# ST_LINK_V2-1.net
KiCad netlist of a schematic drawn in Altium Designer
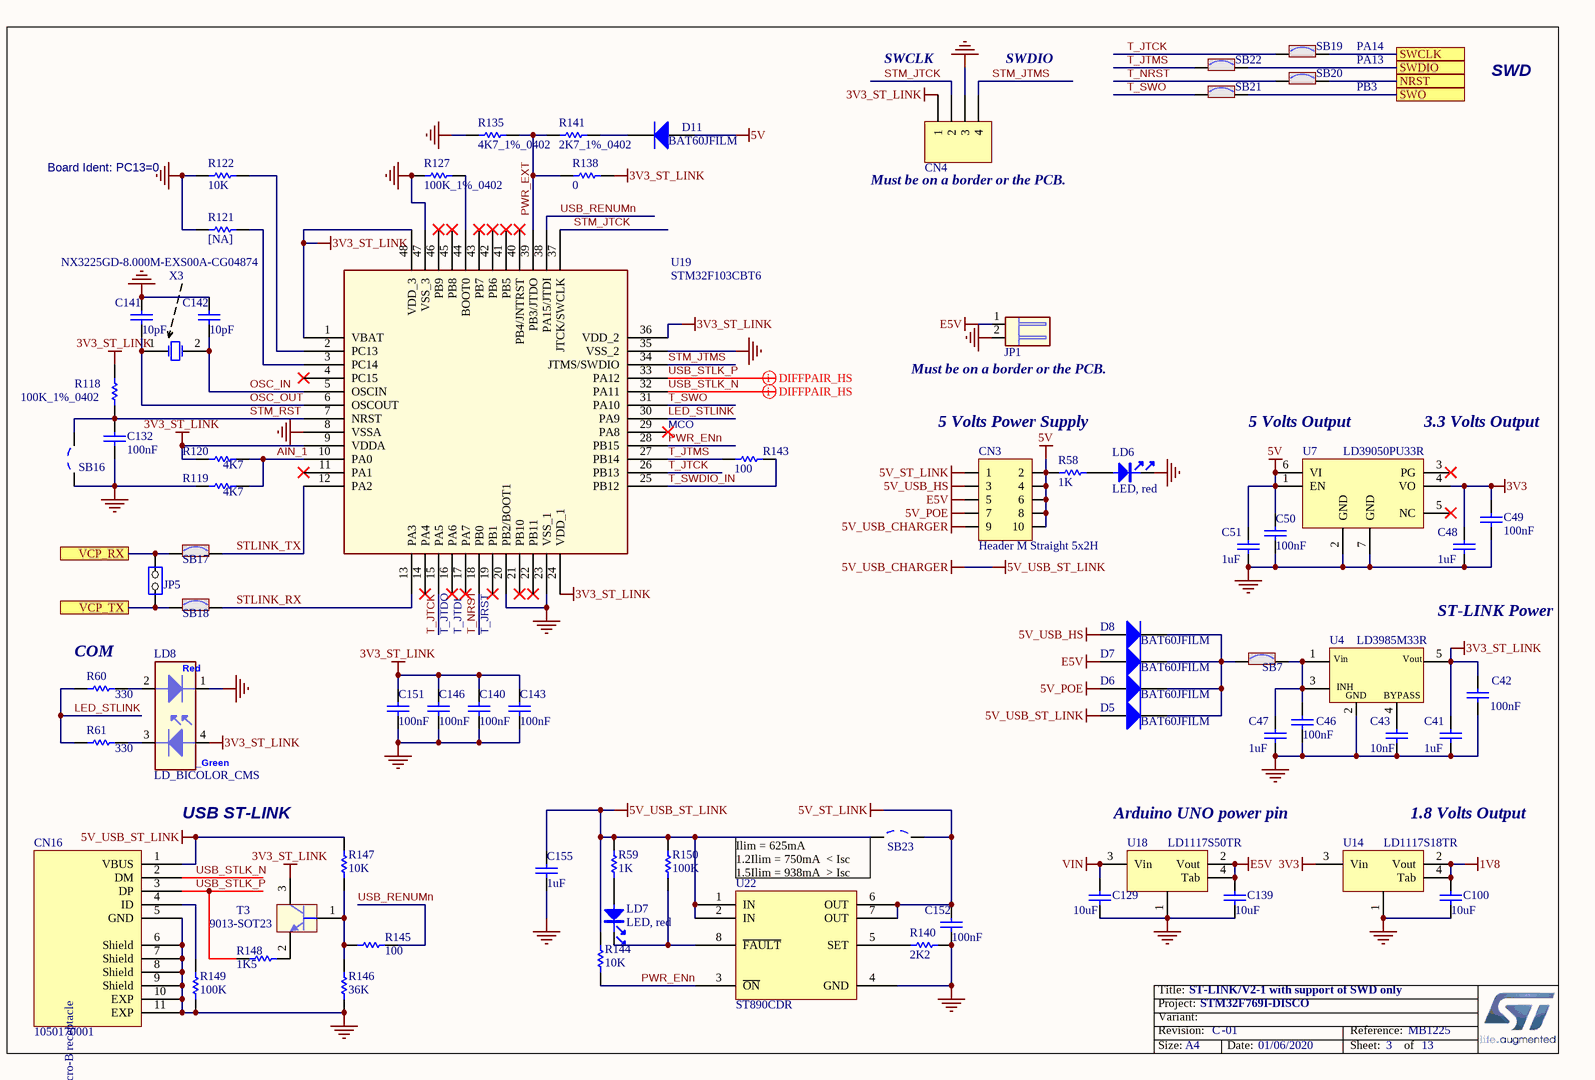
[diagram p0: ST_LINK_V2-1.SCHDOC]

(export (version "E")
  (design (tool "Eeschema 10.0.6"))
  (components
    (comp (ref "C41")
      (value "1uF")
      (footprint "0603C")
      (description "Capacitor,1uF,16V,X5R,10%,0603,YAGEO")
      (libsource (lib "MCD_TOOLS") (part "Cap_1uF_X5R_10%_0603"))
    )
    (comp (ref "C42")
      (value "100nF")
      (footprint "0402C")
      (description "Capacitor,100nF,16V,X7R,10%,0402,YAGEO")
      (libsource (lib "MCD_TOOLS") (part "Cap_100nF_X7R_10%_0402"))
    )
    (comp (ref "C43")
      (value "10nF")
      (footprint "0603C")
      (description "Capacitor,10nF,50V,X7R,10%,0603,YAGEO")
      (libsource (lib "MCD_TOOLS") (part "Cap_10nF_X7R_10%_0603"))
    )
    (comp (ref "C46")
      (value "100nF")
      (footprint "0402C")
      (description "Capacitor,100nF,16V,X7R,10%,0402,YAGEO")
      (libsource (lib "MCD_TOOLS") (part "Cap_100nF_X7R_10%_0402"))
    )
    (comp (ref "C47")
      (value "1uF")
      (footprint "0603C")
      (description "Capacitor,1uF,16V,X5R,10%,0603,YAGEO")
      (libsource (lib "MCD_TOOLS") (part "Cap_1uF_X5R_10%_0603"))
    )
    (comp (ref "C48")
      (value "1uF")
      (footprint "0603C")
      (description "Capacitor,1uF,16V,X5R,10%,0603,YAGEO")
      (libsource (lib "MCD_TOOLS") (part "Cap_1uF_X5R_10%_0603"))
    )
    (comp (ref "C49")
      (value "100nF")
      (footprint "0402C")
      (description "Capacitor,100nF,16V,X7R,10%,0402,YAGEO")
      (libsource (lib "MCD_TOOLS") (part "Cap_100nF_X7R_10%_0402"))
    )
    (comp (ref "C50")
      (value "100nF")
      (footprint "0402C")
      (description "Capacitor,100nF,16V,X7R,10%,0402,YAGEO")
      (libsource (lib "MCD_TOOLS") (part "Cap_100nF_X7R_10%_0402"))
    )
    (comp (ref "C51")
      (value "1uF")
      (footprint "0603C")
      (description "Capacitor,1uF,16V,X5R,10%,0603,YAGEO")
      (libsource (lib "MCD_TOOLS") (part "Cap_1uF_X5R_10%_0603"))
    )
    (comp (ref "C100")
      (value "10uF")
      (footprint "0603C")
      (description "Capacitor,10uF,6.3V,X5R,10%,0603,YAGEO")
      (libsource (lib "MCD_TOOLS") (part "Cap_10uF_X5R_10%_0603"))
    )
    (comp (ref "C129")
      (value "10uF")
      (footprint "0805C")
      (description "Capacitor,10uF,25V,X5R,10%,0805,YAGEO")
      (libsource (lib "MCD_TOOLS") (part "Cap_10uF_X5R_10%_0805"))
    )
    (comp (ref "C132")
      (value "100nF")
      (footprint "0402C")
      (description "Capacitor,100nF,16V,X7R,10%,0402,YAGEO")
      (libsource (lib "MCD_TOOLS") (part "Cap_100nF_X7R_10%_0402"))
    )
    (comp (ref "C139")
      (value "10uF")
      (footprint "0805C")
      (description "Capacitor,10uF,25V,X5R,10%,0805,YAGEO")
      (libsource (lib "MCD_TOOLS") (part "Cap_10uF_X5R_10%_0805"))
    )
    (comp (ref "C140")
      (value "100nF")
      (footprint "0402C")
      (description "Capacitor,100nF,16V,X7R,10%,0402,YAGEO")
      (libsource (lib "MCD_TOOLS") (part "Cap_100nF_X7R_10%_0402"))
    )
    (comp (ref "C141")
      (value "10pF")
      (footprint "0402C")
      (description "Capacitor,10pF,50V,NPO,5%,0402,YAGEO")
      (libsource (lib "MCD_TOOLS") (part "Cap_10pF_NPO_5%_0402"))
    )
    (comp (ref "C142")
      (value "10pF")
      (footprint "0402C")
      (description "Capacitor,10pF,50V,NPO,5%,0402,YAGEO")
      (libsource (lib "MCD_TOOLS") (part "Cap_10pF_NPO_5%_0402"))
    )
    (comp (ref "C143")
      (value "100nF")
      (footprint "0402C")
      (description "Capacitor,100nF,16V,X7R,10%,0402,YAGEO")
      (libsource (lib "MCD_TOOLS") (part "Cap_100nF_X7R_10%_0402"))
    )
    (comp (ref "C146")
      (value "100nF")
      (footprint "0402C")
      (description "Capacitor,100nF,16V,X7R,10%,0402,YAGEO")
      (libsource (lib "MCD_TOOLS") (part "Cap_100nF_X7R_10%_0402"))
    )
    (comp (ref "C151")
      (value "100nF")
      (footprint "0402C")
      (description "Capacitor,100nF,16V,X7R,10%,0402,YAGEO")
      (libsource (lib "MCD_TOOLS") (part "Cap_100nF_X7R_10%_0402"))
    )
    (comp (ref "C152")
      (value "100nF")
      (footprint "0402C")
      (description "Capacitor,100nF,16V,X7R,10%,0402,YAGEO")
      (libsource (lib "MCD_TOOLS") (part "Cap_100nF_X7R_10%_0402"))
    )
    (comp (ref "C155")
      (value "1uF")
      (footprint "0603C")
      (description "Capacitor,1uF,16V,X5R,10%,0603,YAGEO")
      (libsource (lib "MCD_TOOLS_CAPACITOR") (part "Cap_1uF_X5R_10%_0603"))
    )
    (comp (ref "CN3")
      (value "Header M Straight 5x2H")
      (footprint "HDR_2X5_2R54")
      (description "Header Male, 5-Pin, Dual row, Straight, AMD")
      (libsource (lib "MCD_TOOLS_CONNECTOR") (part "Header 5X2M"))
    )
    (comp (ref "CN4")
      (value "Header 4")
      (footprint "HDR_1X4_2R54")
      (description "Header, 4-Pin")
      (fields (field (name "PUBLISHER") "Altium Limited"))
      (libsource (lib "MCD_TOOLS_CONNECTOR") (part "Header 4"))
    )
    (comp (ref "CN16")
      (value "1050170001")
      (footprint "MICRO_USB_B_105017")
      (description "USB-MICRO-B, 1050170001, SMT, MOLEX")
      (libsource (lib "MCD_TOOLS_CONNECTOR") (part "1050170001"))
    )
    (comp (ref "D5")
      (value "BAT60JFILM")
      (footprint "SOD-323")
      (libsource (lib "MCD_TOOLS_MISCELLANEOUS") (part "BAT60JFILM"))
    )
    (comp (ref "D6")
      (value "BAT60JFILM")
      (footprint "SOD-323")
      (libsource (lib "MCD_TOOLS_MISCELLANEOUS") (part "BAT60JFILM"))
    )
    (comp (ref "D7")
      (value "BAT60JFILM")
      (footprint "SOD-323")
      (libsource (lib "MCD_TOOLS_MISCELLANEOUS") (part "BAT60JFILM"))
    )
    (comp (ref "D8")
      (value "BAT60JFILM")
      (footprint "SOD-323")
      (libsource (lib "MCD_TOOLS_MISCELLANEOUS") (part "BAT60JFILM"))
    )
    (comp (ref "D11")
      (value "BAT60JFILM")
      (footprint "SOD-323")
      (libsource (lib "MCD_TOOLS_MISCELLANEOUS") (part "BAT60JFILM"))
    )
    (comp (ref "JP1")
      (value "WF25402-06421")
      (footprint "HDR_1X2_2R54_RA_11R35")
      (description "Header, 2-Pins, Single row, Right Angle, 2.54 mm pitch, DIP")
      (libsource (lib "MCD_TOOLS_CONNECTOR") (part "JP2_RA"))
    )
    (comp (ref "JP5") (value "JP2") (footprint "SIP2") (libsource (lib "MCD_TOOLS_CONNECTOR") (part "JP2")))
    (comp (ref "LD6")
      (value "LED, red")
      (footprint "0603D")
      (description "LED, red, 0603")
      (libsource (lib "MCD_TOOLS") (part "LED_red"))
    )
    (comp (ref "LD7")
      (value "LED, red")
      (footprint "0603D")
      (description "LED, red, 0603")
      (libsource (lib "MCD_TOOLS") (part "LED_red"))
    )
    (comp (ref "LD8")
      (value "LD_BICOLOR_CMS")
      (footprint "LED2_3528")
      (description "Bicolor Led")
      (libsource (lib "MCD_TOOLS_MISCELLANEOUS") (part "LD_BICOLOR_CMS"))
    )
    (comp (ref "R58")
      (value "1K")
      (footprint "0402R")
      (description "Resistor,1K,0402,1%,YAGEO")
      (libsource (lib "MCD_TOOLS") (part "Res_1K_1%_0402"))
    )
    (comp (ref "R59")
      (value "1K")
      (footprint "0402R")
      (description "Resistor,1K,0402,1%,YAGEO")
      (libsource (lib "MCD_TOOLS") (part "Res_1K_1%_0402"))
    )
    (comp (ref "R60")
      (value "330")
      (footprint "0402R")
      (description "Resistor,330,0402,1%,YAGEO")
      (libsource (lib "MCD_TOOLS") (part "Res_330_1%_0402"))
    )
    (comp (ref "R61")
      (value "330")
      (footprint "0402R")
      (description "Resistor,330,0402,1%,YAGEO")
      (libsource (lib "MCD_TOOLS") (part "Res_330_1%_0402"))
    )
    (comp (ref "R118")
      (value "100K_1%_0402")
      (footprint "0402R")
      (description "Resistor,100K,0402,1%,YAGEO")
      (libsource (lib "MCD_TOOLS_RESISTOR") (part "Res_100K_1%_0402"))
    )
    (comp (ref "R119")
      (value "4K7")
      (footprint "0402R")
      (description "Resistor,4K7,0402,1%,YAGEO")
      (libsource (lib "MCD_TOOLS_RESISTOR") (part "Res_4K7_1%_0402"))
    )
    (comp (ref "R120")
      (value "4K7")
      (footprint "0402R")
      (description "Resistor,4K7,0402,1%,YAGEO")
      (libsource (lib "MCD_TOOLS_RESISTOR") (part "Res_4K7_1%_0402"))
    )
    (comp (ref "R121")
      (value "[NA]")
      (footprint "0402R")
      (description "Resistor,[NA],0402")
      (libsource (lib "MCD_TOOLS") (part "Res_NA_0402"))
    )
    (comp (ref "R122")
      (value "10K")
      (footprint "0402R")
      (description "Resistor,10K,0402,1%,YAGEO")
      (libsource (lib "MCD_TOOLS") (part "Res_10K_1%_0402"))
    )
    (comp (ref "R127")
      (value "100K_1%_0402")
      (footprint "0402R")
      (description "Resistor,100K,0402,1%,YAGEO")
      (libsource (lib "MCD_TOOLS_RESISTOR") (part "Res_100K_1%_0402"))
    )
    (comp (ref "R135")
      (value "4K7_1%_0402")
      (footprint "0402R")
      (description "Resistor,4K7,0402,1%,YAGEO")
      (libsource (lib "MCD_TOOLS_RESISTOR") (part "Res_4K7_1%_0402"))
    )
    (comp (ref "R138")
      (value "0")
      (footprint "0402R")
      (description "Resistor,0,0402,5%,YAGEO")
      (libsource (lib "MCD_TOOLS") (part "Res_0_5%_0402"))
    )
    (comp (ref "R140")
      (value "2K2")
      (footprint "0402R")
      (description "Resistor,2K2,0402,1%,YAGEO")
      (libsource (lib "MCD_TOOLS_RESISTOR") (part "Res_2K2_1%_0402"))
    )
    (comp (ref "R141")
      (value "2K7_1%_0402")
      (footprint "0402R")
      (description "Resistor,2K7,0402,1%,YAGEO")
      (libsource (lib "MCD_TOOLS_RESISTOR") (part "Res_2K7_1%_0402"))
    )
    (comp (ref "R143")
      (value "100")
      (footprint "0402R")
      (description "Resistor,100,0402,1%,YAGEO")
      (libsource (lib "MCD_TOOLS") (part "Res_100_1%_0402"))
    )
    (comp (ref "R144")
      (value "10K")
      (footprint "0402R")
      (description "Resistor,10K,0402,1%,YAGEO")
      (libsource (lib "MCD_TOOLS") (part "Res_10K_1%_0402"))
    )
    (comp (ref "R145")
      (value "100")
      (footprint "0402R")
      (description "Resistor,100,0402,1%,YAGEO")
      (libsource (lib "MCD_TOOLS") (part "Res_100_1%_0402"))
    )
    (comp (ref "R146")
      (value "36K")
      (footprint "0402R")
      (description "Resistor,36K,0402,1%,YAGEO")
      (libsource (lib "MCD_TOOLS") (part "Res_36K_1%_0402"))
    )
    (comp (ref "R147")
      (value "10K")
      (footprint "0402R")
      (description "Resistor,10K,0402,1%,YAGEO")
      (libsource (lib "MCD_TOOLS") (part "Res_10K_1%_0402"))
    )
    (comp (ref "R148")
      (value "1K5")
      (footprint "0402R")
      (description "Resistor,1K5,0402,1%,YAGEO")
      (libsource (lib "MCD_TOOLS") (part "Res_1K5_1%_0402"))
    )
    (comp (ref "R149")
      (value "100K")
      (footprint "0402R")
      (description "Resistor,100K,0402,1%,YAGEO")
      (libsource (lib "MCD_TOOLS_RESISTOR") (part "Res_100K_1%_0402"))
    )
    (comp (ref "R150")
      (value "100K")
      (footprint "0402R")
      (description "Resistor,100K,0402,1%,YAGEO")
      (libsource (lib "MCD_TOOLS_RESISTOR") (part "Res_100K_1%_0402"))
    )
    (comp (ref "SB7")
      (value "Solder Bridge ON")
      (footprint "JP2_SMD")
      (libsource (lib "MCD_TOOLS") (part "SB_ON"))
    )
    (comp (ref "SB16")
      (value "Solder Bridge OFF")
      (footprint "JP2_SMD")
      (libsource (lib "MCD_TOOLS") (part "SB_OFF"))
    )
    (comp (ref "SB17")
      (value "Solder Bridge ON")
      (footprint "JP2_SMD")
      (libsource (lib "MCD_TOOLS") (part "SB_ON"))
    )
    (comp (ref "SB18")
      (value "Solder Bridge ON")
      (footprint "JP2_SMD")
      (libsource (lib "MCD_TOOLS") (part "SB_ON"))
    )
    (comp (ref "SB19")
      (value "Solder Bridge ON")
      (footprint "JP2_SMD")
      (libsource (lib "MCD_TOOLS") (part "SB_ON"))
    )
    (comp (ref "SB20")
      (value "Solder Bridge ON")
      (footprint "JP2_SMD")
      (libsource (lib "MCD_TOOLS") (part "SB_ON"))
    )
    (comp (ref "SB21")
      (value "Solder Bridge ON")
      (footprint "JP2_SMD")
      (libsource (lib "MCD_TOOLS") (part "SB_ON"))
    )
    (comp (ref "SB22")
      (value "Solder Bridge ON")
      (footprint "JP2_SMD")
      (libsource (lib "MCD_TOOLS") (part "SB_ON"))
    )
    (comp (ref "SB23")
      (value "Solder Bridge OFF")
      (footprint "JP2_SMD")
      (libsource (lib "MCD_TOOLS") (part "SB_OFF"))
    )
    (comp (ref "T3")
      (value "9013-SOT23")
      (footprint "SOT-23")
      (description "NPN Bipolar Transistor")
      (libsource (lib "MCD_TOOLS_MISCELLANEOUS") (part "9013-SOT23"))
    )
    (comp (ref "U4")
      (value "LD3985M33R")
      (footprint "SOT-23-5L")
      (description "Ultra low drop-low noise BiCMOS voltage, regulators low ESR capacitors compatible")
      (libsource (lib "MCD_TOOLS_MISCELLANEOUS") (part "LD3985M33R"))
    )
    (comp (ref "U7")
      (value "LD39050PU33R")
      (footprint "DFN6_0R95_3X3")
      (description "Ultra low drop-low , 500 mA low quiescent current")
      (libsource (lib "mb1225") (part "LD39050P"))
    )
    (comp (ref "U14")
      (value "LD1117S18TR")
      (footprint "SOT-223")
      (description "LOW DROP FIXED AND ADJUSTABLE POSITIVE VOLTAGE REGULATORS (1.8 Volts)")
      (libsource (lib "mb1225") (part "LD1117S18TR"))
    )
    (comp (ref "U18")
      (value "LD1117S50TR")
      (footprint "SOT-223")
      (description "IC REG LDO 5V 0.8A SOT223")
      (libsource (lib "mb1225") (part "LD1117S50TR"))
    )
    (comp (ref "U19")
      (value "STM32F103CBT6")
      (footprint "LQFP48_0R5_9X9")
      (description "Medium-density performance line ARM-based 32-bit MCU with 128KB Flash")
      (libsource (lib "MCD_TOOLS_MCU") (part "STM32F103CBT6"))
    )
    (comp (ref "U22")
      (value "ST890CDR")
      (footprint "SOIC8_1R27_4R9X6")
      (description "1.2 A current limited high-side power switch with thermal shutdown")
      (libsource (lib "mb1225") (part "ST890CDR"))
    )
    (comp (ref "X3")
      (value "NX3225GD-8.000M-EXS00A-CG04874")
      (footprint "XTAL_2SM_3R2X2R5_H1")
      (description "Crystal 8Mhz, 8pF, -+50PPM, SMD")
      (libsource (lib "MCD_TOOLS_MISCELLANEOUS") (part "XTAL_8M_NX3225GD"))
    )
  )
  (nets
    (net (code "1") (name "/AIN_1") (class "Default")
      (node (ref "R119") (pin "2") (pinfunction "2_2") (pintype "passive"))
      (node (ref "R120") (pin "2") (pinfunction "2_2") (pintype "passive"))
      (node (ref "U19") (pin "10") (pinfunction "PA0_10") (pintype "passive"))
    )
    (net (code "2") (name "/LED_STLINK") (class "Default")
      (node (ref "R60") (pin "1") (pinfunction "1_1") (pintype "passive"))
      (node (ref "R61") (pin "1") (pinfunction "1_1") (pintype "passive"))
      (node (ref "U19") (pin "30") (pinfunction "PA9_30") (pintype "passive"))
    )
    (net (code "3") (name "/NRST") (class "Default")
      (node (ref "SB20") (pin "2") (pinfunction "2_2") (pintype "passive"))
    )
    (net (code "4") (name "/OSC_IN") (class "Default")
      (node (ref "C142") (pin "2") (pinfunction "2_2") (pintype "passive"))
      (node (ref "U19") (pin "5") (pinfunction "OSCIN_5") (pintype "passive"))
      (node (ref "X3") (pin "2") (pinfunction "OSC2_2") (pintype "passive"))
    )
    (net (code "5") (name "/OSC_OUT") (class "Default")
      (node (ref "C141") (pin "2") (pinfunction "2_2") (pintype "passive"))
      (node (ref "U19") (pin "6") (pinfunction "OSCOUT_6") (pintype "passive"))
      (node (ref "X3") (pin "1") (pinfunction "OSC1_1") (pintype "passive"))
    )
    (net (code "6") (name "/PWR_ENn") (class "Default")
      (node (ref "R144") (pin "1") (pinfunction "1_1") (pintype "passive"))
      (node (ref "U19") (pin "28") (pinfunction "PB15_28") (pintype "passive"))
      (node (ref "U22") (pin "3") (pinfunction "~{ON}_3") (pintype "passive"))
    )
    (net (code "7") (name "/PWR_EXT") (class "Default")
      (node (ref "R135") (pin "2") (pinfunction "2_2") (pintype "passive"))
      (node (ref "R138") (pin "1") (pinfunction "1_1") (pintype "passive"))
      (node (ref "R141") (pin "1") (pinfunction "1_1") (pintype "passive"))
      (node (ref "U19") (pin "39") (pinfunction "PB3/JTDO_39") (pintype "passive"))
    )
    (net (code "8") (name "/STLINK_RX") (class "Default")
      (node (ref "SB18") (pin "2") (pinfunction "2_2") (pintype "passive"))
      (node (ref "U19") (pin "13") (pinfunction "PA3_13") (pintype "passive"))
    )
    (net (code "9") (name "/STLINK_TX") (class "Default")
      (node (ref "SB17") (pin "2") (pinfunction "2_2") (pintype "passive"))
      (node (ref "U19") (pin "12") (pinfunction "PA2_12") (pintype "passive"))
    )
    (net (code "10") (name "/STM_JTCK") (class "Default")
      (node (ref "CN4") (pin "2") (pinfunction "2_2") (pintype "passive"))
      (node (ref "U19") (pin "37") (pinfunction "JTCK/SWCLK_37") (pintype "passive"))
    )
    (net (code "11") (name "/STM_JTMS") (class "Default")
      (node (ref "CN4") (pin "4") (pinfunction "4_4") (pintype "passive"))
      (node (ref "U19") (pin "34") (pinfunction "JTMS/SWDIO_34") (pintype "passive"))
    )
    (net (code "12") (name "/STM_RST") (class "Default")
      (node (ref "C132") (pin "2") (pinfunction "2_2") (pintype "passive"))
      (node (ref "R118") (pin "1") (pinfunction "1_1") (pintype "passive"))
      (node (ref "SB16") (pin "2") (pinfunction "2_2") (pintype "passive"))
      (node (ref "U19") (pin "7") (pinfunction "NRST_7") (pintype "passive"))
    )
    (net (code "13") (name "/SWCLK") (class "Default")
      (node (ref "SB19") (pin "2") (pinfunction "2_2") (pintype "passive"))
    )
    (net (code "14") (name "/SWDIO") (class "Default")
      (node (ref "SB22") (pin "2") (pinfunction "2_2") (pintype "passive"))
    )
    (net (code "15") (name "/SWO") (class "Default")
      (node (ref "SB21") (pin "2") (pinfunction "2_2") (pintype "passive"))
    )
    (net (code "16") (name "/T_JTCK") (class "Default")
      (node (ref "SB19") (pin "1") (pinfunction "1_1") (pintype "passive"))
      (node (ref "U19") (pin "15") (pinfunction "PA5_15") (pintype "passive"))
      (node (ref "U19") (pin "26") (pinfunction "PB13_26") (pintype "passive"))
    )
    (net (code "17") (name "/T_JTMS") (class "Default")
      (node (ref "R143") (pin "1") (pinfunction "1_1") (pintype "passive"))
      (node (ref "SB22") (pin "1") (pinfunction "1_1") (pintype "passive"))
      (node (ref "U19") (pin "27") (pinfunction "PB14_27") (pintype "passive"))
    )
    (net (code "18") (name "/T_NRST") (class "Default")
      (node (ref "SB20") (pin "1") (pinfunction "1_1") (pintype "passive"))
      (node (ref "U19") (pin "18") (pinfunction "PB0_18") (pintype "passive"))
    )
    (net (code "19") (name "/T_SWDIO_IN") (class "Default")
      (node (ref "R143") (pin "2") (pinfunction "2_2") (pintype "passive"))
      (node (ref "U19") (pin "25") (pinfunction "PB12_25") (pintype "passive"))
    )
    (net (code "20") (name "/T_SWO") (class "Default")
      (node (ref "SB21") (pin "1") (pinfunction "1_1") (pintype "passive"))
      (node (ref "U19") (pin "31") (pinfunction "PA10_31") (pintype "passive"))
    )
    (net (code "21") (name "/USB_RENUMn") (class "Default")
      (node (ref "R145") (pin "2") (pinfunction "2_2") (pintype "passive"))
      (node (ref "U19") (pin "38") (pinfunction "PA15/JTDI_38") (pintype "passive"))
    )
    (net (code "22") (name "/USB_STLK_N") (class "Default")
      (node (ref "CN16") (pin "2") (pinfunction "DM_2") (pintype "passive"))
      (node (ref "U19") (pin "32") (pinfunction "PA11_32") (pintype "passive"))
    )
    (net (code "23") (name "/USB_STLK_P") (class "Default")
      (node (ref "CN16") (pin "3") (pinfunction "DP_3") (pintype "passive"))
      (node (ref "R148") (pin "1") (pinfunction "1_1") (pintype "passive"))
      (node (ref "U19") (pin "33") (pinfunction "PA12_33") (pintype "passive"))
    )
    (net (code "24") (name "/VCP_RX") (class "Default")
      (node (ref "JP5") (pin "2") (pinfunction "NO_2") (pintype "passive"))
      (node (ref "SB17") (pin "1") (pinfunction "1_1") (pintype "passive"))
    )
    (net (code "25") (name "/VCP_TX") (class "Default")
      (node (ref "JP5") (pin "1") (pinfunction "COMMON_1") (pintype "passive"))
      (node (ref "SB18") (pin "1") (pinfunction "1_1") (pintype "passive"))
    )
    (net (code "26") (name "1V8") (class "Default")
      (node (ref "C100") (pin "2") (pinfunction "2_2") (pintype "passive"))
      (node (ref "U14") (pin "2") (pinfunction "Vout_2") (pintype "passive"))
      (node (ref "U14") (pin "4") (pinfunction "Tab_4") (pintype "passive"))
    )
    (net (code "27") (name "3V3") (class "Default")
      (node (ref "C48") (pin "2") (pinfunction "2_2") (pintype "passive"))
      (node (ref "C49") (pin "2") (pinfunction "2_2") (pintype "passive"))
      (node (ref "U14") (pin "3") (pinfunction "Vin_3") (pintype "passive"))
      (node (ref "U7") (pin "4") (pinfunction "VO_4") (pintype "passive"))
    )
    (net (code "28") (name "3V3_ST_LINK") (class "Default")
      (node (ref "C140") (pin "1") (pinfunction "1_1") (pintype "passive"))
      (node (ref "C143") (pin "2") (pinfunction "2_2") (pintype "passive"))
      (node (ref "C146") (pin "2") (pinfunction "2_2") (pintype "passive"))
      (node (ref "C151") (pin "2") (pinfunction "2_2") (pintype "passive"))
      (node (ref "C41") (pin "1") (pinfunction "1_1") (pintype "passive"))
      (node (ref "C42") (pin "2") (pinfunction "2_2") (pintype "passive"))
      (node (ref "CN4") (pin "1") (pinfunction "1_1") (pintype "passive"))
      (node (ref "LD8") (pin "4") (pinfunction "4_4") (pintype "passive"))
      (node (ref "R118") (pin "2") (pinfunction "2_2") (pintype "passive"))
      (node (ref "R120") (pin "1") (pinfunction "1_1") (pintype "passive"))
      (node (ref "R138") (pin "2") (pinfunction "2_2") (pintype "passive"))
      (node (ref "T3") (pin "3") (pinfunction "C_3") (pintype "passive"))
      (node (ref "U19") (pin "1") (pinfunction "VBAT_1") (pintype "passive"))
      (node (ref "U19") (pin "24") (pinfunction "VDD_1_24") (pintype "passive"))
      (node (ref "U19") (pin "36") (pinfunction "VDD_2_36") (pintype "passive"))
      (node (ref "U19") (pin "48") (pinfunction "VDD_3_48") (pintype "passive"))
      (node (ref "U19") (pin "9") (pinfunction "VDDA_9") (pintype "passive"))
      (node (ref "U4") (pin "5") (pinfunction "Vout_5") (pintype "passive"))
    )
    (net (code "29") (name "5V") (class "Default")
      (node (ref "C50") (pin "2") (pinfunction "2_2") (pintype "passive"))
      (node (ref "C51") (pin "2") (pinfunction "2_2") (pintype "passive"))
      (node (ref "CN3") (pin "10") (pinfunction "10_10") (pintype "passive"))
      (node (ref "CN3") (pin "2") (pinfunction "2_2") (pintype "passive"))
      (node (ref "CN3") (pin "4") (pinfunction "4_4") (pintype "passive"))
      (node (ref "CN3") (pin "6") (pinfunction "6_6") (pintype "passive"))
      (node (ref "CN3") (pin "8") (pinfunction "8_8") (pintype "passive"))
      (node (ref "D11") (pin "1") (pinfunction "A_1") (pintype "passive"))
      (node (ref "R58") (pin "1") (pinfunction "1_1") (pintype "passive"))
      (node (ref "U7") (pin "1") (pinfunction "EN_1") (pintype "passive"))
      (node (ref "U7") (pin "6") (pinfunction "VI_6") (pintype "passive"))
    )
    (net (code "30") (name "5V_POE") (class "Default")
      (node (ref "CN3") (pin "7") (pinfunction "7_7") (pintype "passive"))
      (node (ref "D6") (pin "1") (pinfunction "A_1") (pintype "passive"))
    )
    (net (code "31") (name "5V_ST_LINK") (class "Default")
      (node (ref "C152") (pin "2") (pinfunction "2_2") (pintype "passive"))
      (node (ref "CN3") (pin "1") (pinfunction "1_1") (pintype "passive"))
      (node (ref "SB23") (pin "2") (pinfunction "2_2") (pintype "passive"))
      (node (ref "U22") (pin "6") (pinfunction "OUT_6") (pintype "passive"))
      (node (ref "U22") (pin "7") (pinfunction "OUT_7") (pintype "passive"))
    )
    (net (code "32") (name "5V_USB_CHARGER") (class "Default")
      (node (ref "C155") (pin "2") (pinfunction "2_2") (pintype "passive"))
      (node (ref "CN16") (pin "1") (pinfunction "VBUS_1") (pintype "passive"))
      (node (ref "CN3") (pin "9") (pinfunction "9_9") (pintype "passive"))
      (node (ref "D5") (pin "1") (pinfunction "A_1") (pintype "passive"))
      (node (ref "R144") (pin "2") (pinfunction "2_2") (pintype "passive"))
      (node (ref "R147") (pin "2") (pinfunction "2_2") (pintype "passive"))
      (node (ref "R150") (pin "2") (pinfunction "2_2") (pintype "passive"))
      (node (ref "R59") (pin "2") (pinfunction "2_2") (pintype "passive"))
      (node (ref "SB23") (pin "1") (pinfunction "1_1") (pintype "passive"))
      (node (ref "U22") (pin "1") (pinfunction "IN_1") (pintype "passive"))
      (node (ref "U22") (pin "2") (pinfunction "IN_2") (pintype "passive"))
    )
    (net (code "33") (name "5V_USB_HS") (class "Default")
      (node (ref "CN3") (pin "3") (pinfunction "3_3") (pintype "passive"))
      (node (ref "D8") (pin "1") (pinfunction "A_1") (pintype "passive"))
    )
    (net (code "34") (name "E5V") (class "Default")
      (node (ref "C139") (pin "2") (pinfunction "2_2") (pintype "passive"))
      (node (ref "CN3") (pin "5") (pinfunction "5_5") (pintype "passive"))
      (node (ref "D7") (pin "1") (pinfunction "A_1") (pintype "passive"))
      (node (ref "JP1") (pin "1") (pinfunction "1_1") (pintype "passive"))
      (node (ref "U18") (pin "2") (pinfunction "Vout_2") (pintype "passive"))
      (node (ref "U18") (pin "4") (pinfunction "Tab_4") (pintype "passive"))
    )
    (net (code "35") (name "GND") (class "Default")
      (node (ref "C100") (pin "1") (pinfunction "1_1") (pintype "passive"))
      (node (ref "C129") (pin "1") (pinfunction "1_1") (pintype "passive"))
      (node (ref "C132") (pin "1") (pinfunction "1_1") (pintype "passive"))
      (node (ref "C139") (pin "1") (pinfunction "1_1") (pintype "passive"))
      (node (ref "C140") (pin "2") (pinfunction "2_2") (pintype "passive"))
      (node (ref "C141") (pin "1") (pinfunction "1_1") (pintype "passive"))
      (node (ref "C142") (pin "1") (pinfunction "1_1") (pintype "passive"))
      (node (ref "C143") (pin "1") (pinfunction "1_1") (pintype "passive"))
      (node (ref "C146") (pin "1") (pinfunction "1_1") (pintype "passive"))
      (node (ref "C151") (pin "1") (pinfunction "1_1") (pintype "passive"))
      (node (ref "C152") (pin "1") (pinfunction "1_1") (pintype "passive"))
      (node (ref "C155") (pin "1") (pinfunction "1_1") (pintype "passive"))
      (node (ref "C41") (pin "2") (pinfunction "2_2") (pintype "passive"))
      (node (ref "C42") (pin "1") (pinfunction "1_1") (pintype "passive"))
      (node (ref "C43") (pin "1") (pinfunction "1_1") (pintype "passive"))
      (node (ref "C46") (pin "1") (pinfunction "1_1") (pintype "passive"))
      (node (ref "C47") (pin "1") (pinfunction "1_1") (pintype "passive"))
      (node (ref "C48") (pin "1") (pinfunction "1_1") (pintype "passive"))
      (node (ref "C49") (pin "1") (pinfunction "1_1") (pintype "passive"))
      (node (ref "C50") (pin "1") (pinfunction "1_1") (pintype "passive"))
      (node (ref "C51") (pin "1") (pinfunction "1_1") (pintype "passive"))
      (node (ref "CN16") (pin "10") (pinfunction "EXP_10") (pintype "passive"))
      (node (ref "CN16") (pin "11") (pinfunction "EXP_11") (pintype "passive"))
      (node (ref "CN16") (pin "5") (pinfunction "GND_5") (pintype "passive"))
      (node (ref "CN16") (pin "6") (pinfunction "Shield_6") (pintype "passive"))
      (node (ref "CN16") (pin "7") (pinfunction "Shield_7") (pintype "passive"))
      (node (ref "CN16") (pin "8") (pinfunction "Shield_8") (pintype "passive"))
      (node (ref "CN16") (pin "9") (pinfunction "Shield_9") (pintype "passive"))
      (node (ref "CN4") (pin "3") (pinfunction "3_3") (pintype "passive"))
      (node (ref "JP1") (pin "2") (pinfunction "2_2") (pintype "passive"))
      (node (ref "LD6") (pin "2") (pintype "passive"))
      (node (ref "LD8") (pin "1") (pinfunction "1_1") (pintype "passive"))
      (node (ref "R119") (pin "1") (pinfunction "1_1") (pintype "passive"))
      (node (ref "R121") (pin "1") (pinfunction "1_1") (pintype "passive"))
      (node (ref "R122") (pin "1") (pinfunction "1_1") (pintype "passive"))
      (node (ref "R127") (pin "1") (pinfunction "1_1") (pintype "passive"))
      (node (ref "R135") (pin "1") (pinfunction "1_1") (pintype "passive"))
      (node (ref "R140") (pin "2") (pinfunction "2_2") (pintype "passive"))
      (node (ref "R146") (pin "1") (pinfunction "1_1") (pintype "passive"))
      (node (ref "R149") (pin "1") (pinfunction "1_1") (pintype "passive"))
      (node (ref "SB16") (pin "1") (pinfunction "1_1") (pintype "passive"))
      (node (ref "U14") (pin "1") (pintype "passive"))
      (node (ref "U18") (pin "1") (pintype "passive"))
      (node (ref "U19") (pin "20") (pinfunction "PB2/BOOT1_20") (pintype "passive"))
      (node (ref "U19") (pin "23") (pinfunction "VSS_1_23") (pintype "passive"))
      (node (ref "U19") (pin "35") (pinfunction "VSS_2_35") (pintype "passive"))
      (node (ref "U19") (pin "47") (pinfunction "VSS_3_47") (pintype "passive"))
      (node (ref "U19") (pin "8") (pinfunction "VSSA_8") (pintype "passive"))
      (node (ref "U22") (pin "4") (pinfunction "GND_4") (pintype "passive"))
      (node (ref "U4") (pin "2") (pinfunction "GND_2") (pintype "passive"))
      (node (ref "U7") (pin "2") (pinfunction "GND_2") (pintype "passive"))
      (node (ref "U7") (pin "7") (pinfunction "GND_7") (pintype "passive"))
    )
    (net (code "36") (name "Net-(CN16-ID)") (class "Default")
      (node (ref "CN16") (pin "4") (pinfunction "ID_4") (pintype "passive"))
      (node (ref "R149") (pin "2") (pinfunction "2_2") (pintype "passive"))
    )
    (net (code "37") (name "Net-(D5-K)") (class "Default")
      (node (ref "D5") (pin "2") (pinfunction "K_2") (pintype "passive"))
      (node (ref "D6") (pin "2") (pinfunction "K_2") (pintype "passive"))
      (node (ref "D7") (pin "2") (pinfunction "K_2") (pintype "passive"))
      (node (ref "D8") (pin "2") (pinfunction "K_2") (pintype "passive"))
      (node (ref "SB7") (pin "1") (pinfunction "1_1") (pintype "passive"))
    )
    (net (code "38") (name "Net-(D11-K)") (class "Default")
      (node (ref "D11") (pin "2") (pinfunction "K_2") (pintype "passive"))
      (node (ref "R141") (pin "2") (pinfunction "2_2") (pintype "passive"))
    )
    (net (code "39") (name "Net-(LD6-Pad1)") (class "Default")
      (node (ref "LD6") (pin "1") (pintype "passive"))
      (node (ref "R58") (pin "2") (pinfunction "2_2") (pintype "passive"))
    )
    (net (code "40") (name "Net-(LD7-Pad1)") (class "Default")
      (node (ref "LD7") (pin "1") (pintype "passive"))
      (node (ref "R59") (pin "1") (pinfunction "1_1") (pintype "passive"))
    )
    (net (code "41") (name "Net-(LD8-Pad2)") (class "Default")
      (node (ref "LD8") (pin "2") (pinfunction "2_2") (pintype "passive"))
      (node (ref "R60") (pin "2") (pinfunction "2_2") (pintype "passive"))
    )
    (net (code "42") (name "Net-(LD8-Pad3)") (class "Default")
      (node (ref "LD8") (pin "3") (pinfunction "3_3") (pintype "passive"))
      (node (ref "R61") (pin "2") (pinfunction "2_2") (pintype "passive"))
    )
    (net (code "43") (name "Net-(T3-B)") (class "Default")
      (node (ref "R145") (pin "1") (pinfunction "1_1") (pintype "passive"))
      (node (ref "R146") (pin "2") (pinfunction "2_2") (pintype "passive"))
      (node (ref "R147") (pin "1") (pinfunction "1_1") (pintype "passive"))
      (node (ref "T3") (pin "1") (pinfunction "B_1") (pintype "passive"))
    )
    (net (code "44") (name "Net-(T3-E)") (class "Default")
      (node (ref "R148") (pin "2") (pinfunction "2_2") (pintype "passive"))
      (node (ref "T3") (pin "2") (pinfunction "E_2") (pintype "passive"))
    )
    (net (code "45") (name "Net-(U4-BYPASS)") (class "Default")
      (node (ref "C43") (pin "2") (pinfunction "2_2") (pintype "passive"))
      (node (ref "U4") (pin "4") (pinfunction "BYPASS_4") (pintype "passive"))
    )
    (net (code "46") (name "Net-(U4-CE)") (class "Default")
      (node (ref "C46") (pin "2") (pinfunction "2_2") (pintype "passive"))
      (node (ref "C47") (pin "2") (pinfunction "2_2") (pintype "passive"))
      (node (ref "SB7") (pin "2") (pinfunction "2_2") (pintype "passive"))
      (node (ref "U4") (pin "1") (pinfunction "Vin_1") (pintype "passive"))
      (node (ref "U4") (pin "3") (pinfunction "CE_3") (pintype "passive"))
    )
    (net (code "47") (name "Net-(U19-BOOT0)") (class "Default")
      (node (ref "R127") (pin "2") (pinfunction "2_2") (pintype "passive"))
      (node (ref "U19") (pin "44") (pinfunction "BOOT0_44") (pintype "passive"))
    )
    (net (code "48") (name "Net-(U19-PC13)") (class "Default")
      (node (ref "R122") (pin "2") (pinfunction "2_2") (pintype "passive"))
      (node (ref "U19") (pin "2") (pinfunction "PC13_2") (pintype "passive"))
    )
    (net (code "49") (name "Net-(U19-PC14)") (class "Default")
      (node (ref "R121") (pin "2") (pinfunction "2_2") (pintype "passive"))
      (node (ref "U19") (pin "3") (pinfunction "PC14_3") (pintype "passive"))
    )
    (net (code "50") (name "Net-(U22-SET)") (class "Default")
      (node (ref "R140") (pin "1") (pinfunction "1_1") (pintype "passive"))
      (node (ref "U22") (pin "5") (pinfunction "SET_5") (pintype "passive"))
    )
    (net (code "51") (name "Net-(U22-~{FAULT})") (class "Default")
      (node (ref "LD7") (pin "2") (pintype "passive"))
      (node (ref "R150") (pin "1") (pinfunction "1_1") (pintype "passive"))
      (node (ref "U22") (pin "8") (pinfunction "~{FAULT}_8") (pintype "passive"))
    )
    (net (code "52") (name "VIN") (class "Default")
      (node (ref "C129") (pin "2") (pinfunction "2_2") (pintype "passive"))
      (node (ref "U18") (pin "3") (pinfunction "Vin_3") (pintype "passive"))
    )
    (net (code "53") (name "unconnected-(U7-NC-Pad5)") (class "Default")
      (node (ref "U7") (pin "5") (pinfunction "NC_5") (pintype "passive+no_connect"))
    )
    (net (code "54") (name "unconnected-(U7-PG-Pad3)") (class "Default")
      (node (ref "U7") (pin "3") (pinfunction "PG_3") (pintype "passive+no_connect"))
    )
    (net (code "55") (name "unconnected-(U19-PA1-Pad11)") (class "Default")
      (node (ref "U19") (pin "11") (pinfunction "PA1_11") (pintype "passive+no_connect"))
    )
    (net (code "56") (name "unconnected-(U19-PA4-Pad14)") (class "Default")
      (node (ref "U19") (pin "14") (pinfunction "PA4_14") (pintype "passive+no_connect"))
    )
    (net (code "57") (name "unconnected-(U19-PA6-Pad16)") (class "Default")
      (node (ref "U19") (pin "16") (pinfunction "PA6_16") (pintype "passive+no_connect"))
    )
    (net (code "58") (name "unconnected-(U19-PA7-Pad17)") (class "Default")
      (node (ref "U19") (pin "17") (pinfunction "PA7_17") (pintype "passive+no_connect"))
    )
    (net (code "59") (name "unconnected-(U19-PA8-Pad29)") (class "Default")
      (node (ref "U19") (pin "29") (pinfunction "PA8_29") (pintype "passive+no_connect"))
    )
    (net (code "60") (name "unconnected-(U19-PB1-Pad19)") (class "Default")
      (node (ref "U19") (pin "19") (pinfunction "PB1_19") (pintype "passive+no_connect"))
    )
    (net (code "61") (name "unconnected-(U19-PB4{slash}JNTRST-Pad40)") (class "Default")
      (node (ref "U19") (pin "40") (pinfunction "PB4/JNTRST_40") (pintype "passive+no_connect"))
    )
    (net (code "62") (name "unconnected-(U19-PB5-Pad41)") (class "Default")
      (node (ref "U19") (pin "41") (pinfunction "PB5_41") (pintype "passive+no_connect"))
    )
    (net (code "63") (name "unconnected-(U19-PB6-Pad42)") (class "Default")
      (node (ref "U19") (pin "42") (pinfunction "PB6_42") (pintype "passive+no_connect"))
    )
    (net (code "64") (name "unconnected-(U19-PB7-Pad43)") (class "Default")
      (node (ref "U19") (pin "43") (pinfunction "PB7_43") (pintype "passive+no_connect"))
    )
    (net (code "65") (name "unconnected-(U19-PB8-Pad45)") (class "Default")
      (node (ref "U19") (pin "45") (pinfunction "PB8_45") (pintype "passive+no_connect"))
    )
    (net (code "66") (name "unconnected-(U19-PB9-Pad46)") (class "Default")
      (node (ref "U19") (pin "46") (pinfunction "PB9_46") (pintype "passive+no_connect"))
    )
    (net (code "67") (name "unconnected-(U19-PB10-Pad21)") (class "Default")
      (node (ref "U19") (pin "21") (pinfunction "PB10_21") (pintype "passive+no_connect"))
    )
    (net (code "68") (name "unconnected-(U19-PB11-Pad22)") (class "Default")
      (node (ref "U19") (pin "22") (pinfunction "PB11_22") (pintype "passive+no_connect"))
    )
    (net (code "69") (name "unconnected-(U19-PC15-Pad4)") (class "Default")
      (node (ref "U19") (pin "4") (pinfunction "PC15_4") (pintype "passive+no_connect"))
    )
  )
)
